# mood_ring.net
KiCad netlist of a schematic drawn in EAGLE
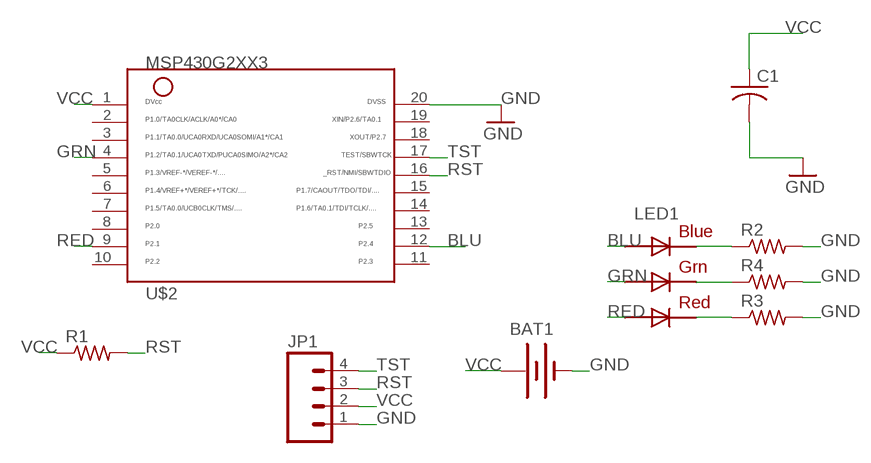
[diagram p0: schematic, sheet 1]

(export (version "E")
  (design (tool "Eeschema 10.0.6"))
  (components
    (comp (ref "BAT1")
      (value "BATTERYBU2032SM")
      (footprint "eagle-import:BU2032SM")
      (libsource (lib "eagle-import") (part "BATTERYBU2032SM"))
    )
    (comp (ref "C1")
      (value "C-USC1206")
      (footprint "eagle-import:C1206")
      (libsource (lib "eagle-import") (part "C-USC1206"))
    )
    (comp (ref "JP1")
      (value "M04LOCK")
      (footprint "eagle-import:1X04_LOCK")
      (libsource (lib "eagle-import") (part "M04LOCK"))
    )
    (comp (ref "LED1")
      (value "RGBLED5050")
      (footprint "eagle-import:RGBLED5050")
      (libsource (lib "eagle-import") (part "RGBLED5050"))
    )
    (comp (ref "R1")
      (value "R-US_R1206")
      (footprint "eagle-import:R1206")
      (libsource (lib "eagle-import") (part "R-US_R1206"))
    )
    (comp (ref "R2")
      (value "R-US_R1206")
      (footprint "eagle-import:R1206")
      (libsource (lib "eagle-import") (part "R-US_R1206"))
    )
    (comp (ref "R3")
      (value "R-US_R1206")
      (footprint "eagle-import:R1206")
      (libsource (lib "eagle-import") (part "R-US_R1206"))
    )
    (comp (ref "R4")
      (value "R-US_R1206")
      (footprint "eagle-import:R1206")
      (libsource (lib "eagle-import") (part "R-US_R1206"))
    )
    (comp (ref "U$2")
      (value "MSP430G2XX3TSSOP")
      (footprint "eagle-import:PW20")
      (libsource (lib "eagle-import") (part "MSP430G2XX3TSSOP"))
    )
  )
  (nets
    (net (code "1") (name "/BLU") (class "Default")
      (node (ref "LED1") (pin "3") (pinfunction "BLUE_A_3") (pintype "bidirectional"))
      (node (ref "U$2") (pin "12") (pinfunction "12_12") (pintype "bidirectional"))
    )
    (net (code "2") (name "/GRN") (class "Default")
      (node (ref "LED1") (pin "1") (pinfunction "GREEN_A_1") (pintype "bidirectional"))
      (node (ref "U$2") (pin "4") (pinfunction "4_4") (pintype "bidirectional"))
    )
    (net (code "3") (name "/RED") (class "Default")
      (node (ref "LED1") (pin "2") (pinfunction "RED_A_2") (pintype "bidirectional"))
      (node (ref "U$2") (pin "9") (pinfunction "9_9") (pintype "bidirectional"))
    )
    (net (code "4") (name "/RST") (class "Default")
      (node (ref "JP1") (pin "3") (pinfunction "3_3") (pintype "passive"))
      (node (ref "R1") (pin "2") (pinfunction "2_2") (pintype "passive"))
      (node (ref "U$2") (pin "16") (pinfunction "16_16") (pintype "bidirectional"))
    )
    (net (code "5") (name "/TST") (class "Default")
      (node (ref "JP1") (pin "4") (pinfunction "4_4") (pintype "passive"))
      (node (ref "U$2") (pin "17") (pinfunction "17_17") (pintype "bidirectional"))
    )
    (net (code "6") (name "/VCC") (class "Default")
      (node (ref "BAT1") (pin "P$1") (pinfunction "+_P$1") (pintype "power_in"))
      (node (ref "C1") (pin "1") (pinfunction "1_1") (pintype "passive"))
      (node (ref "JP1") (pin "2") (pinfunction "2_2") (pintype "passive"))
      (node (ref "R1") (pin "1") (pinfunction "1_1") (pintype "passive"))
      (node (ref "U$2") (pin "1") (pinfunction "1_1") (pintype "bidirectional"))
    )
    (net (code "7") (name "GND") (class "Default")
      (node (ref "BAT1") (pin "P$2") (pinfunction "-_P$2") (pintype "power_in"))
      (node (ref "C1") (pin "2") (pinfunction "2_2") (pintype "passive"))
      (node (ref "JP1") (pin "1") (pinfunction "1_1") (pintype "passive"))
      (node (ref "R2") (pin "2") (pinfunction "2_2") (pintype "passive"))
      (node (ref "R3") (pin "2") (pinfunction "2_2") (pintype "passive"))
      (node (ref "R4") (pin "2") (pinfunction "2_2") (pintype "passive"))
      (node (ref "U$2") (pin "20") (pinfunction "20_20") (pintype "bidirectional"))
    )
    (net (code "8") (name "Net-(LED1-BLUE_C)") (class "Default")
      (node (ref "LED1") (pin "4") (pinfunction "BLUE_C_4") (pintype "bidirectional"))
      (node (ref "R2") (pin "1") (pinfunction "1_1") (pintype "passive"))
    )
    (net (code "9") (name "Net-(LED1-GREEN_C)") (class "Default")
      (node (ref "LED1") (pin "6") (pinfunction "GREEN_C_6") (pintype "bidirectional"))
      (node (ref "R4") (pin "1") (pinfunction "1_1") (pintype "passive"))
    )
    (net (code "10") (name "Net-(LED1-RED_C)") (class "Default")
      (node (ref "LED1") (pin "5") (pinfunction "RED_C_5") (pintype "bidirectional"))
      (node (ref "R3") (pin "1") (pinfunction "1_1") (pintype "passive"))
    )
    (net (code "11") (name "unconnected-(U$2-Pad2)") (class "Default")
      (node (ref "U$2") (pin "2") (pinfunction "2_2") (pintype "bidirectional"))
    )
    (net (code "12") (name "unconnected-(U$2-Pad3)") (class "Default")
      (node (ref "U$2") (pin "3") (pinfunction "3_3") (pintype "bidirectional"))
    )
    (net (code "13") (name "unconnected-(U$2-Pad5)") (class "Default")
      (node (ref "U$2") (pin "5") (pinfunction "5_5") (pintype "bidirectional"))
    )
    (net (code "14") (name "unconnected-(U$2-Pad6)") (class "Default")
      (node (ref "U$2") (pin "6") (pinfunction "6_6") (pintype "bidirectional"))
    )
    (net (code "15") (name "unconnected-(U$2-Pad7)") (class "Default")
      (node (ref "U$2") (pin "7") (pinfunction "7_7") (pintype "bidirectional"))
    )
    (net (code "16") (name "unconnected-(U$2-Pad8)") (class "Default")
      (node (ref "U$2") (pin "8") (pinfunction "8_8") (pintype "bidirectional"))
    )
    (net (code "17") (name "unconnected-(U$2-Pad10)") (class "Default")
      (node (ref "U$2") (pin "10") (pinfunction "10_10") (pintype "bidirectional"))
    )
    (net (code "18") (name "unconnected-(U$2-Pad11)") (class "Default")
      (node (ref "U$2") (pin "11") (pinfunction "11_11") (pintype "bidirectional"))
    )
    (net (code "19") (name "unconnected-(U$2-Pad13)") (class "Default")
      (node (ref "U$2") (pin "13") (pinfunction "13_13") (pintype "bidirectional"))
    )
    (net (code "20") (name "unconnected-(U$2-Pad14)") (class "Default")
      (node (ref "U$2") (pin "14") (pinfunction "14_14") (pintype "bidirectional"))
    )
    (net (code "21") (name "unconnected-(U$2-Pad15)") (class "Default")
      (node (ref "U$2") (pin "15") (pinfunction "15_15") (pintype "bidirectional"))
    )
    (net (code "22") (name "unconnected-(U$2-Pad18)") (class "Default")
      (node (ref "U$2") (pin "18") (pinfunction "18_18") (pintype "bidirectional"))
    )
    (net (code "23") (name "unconnected-(U$2-Pad19)") (class "Default")
      (node (ref "U$2") (pin "19") (pinfunction "19_19") (pintype "bidirectional"))
    )
  )
)
